# I2C.net
KiCad netlist of a schematic drawn in Altium Designer
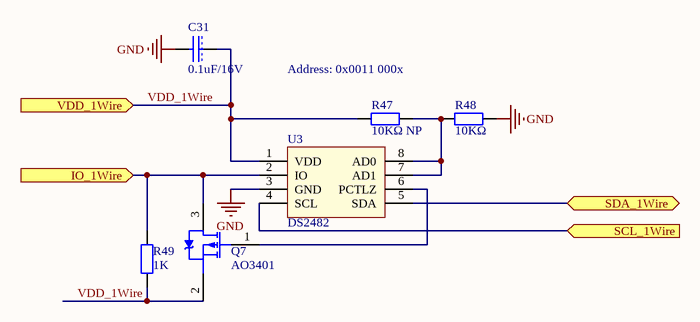
[diagram p0: I2C.SchDoc]

(export (version "E")
  (design (tool "Eeschema 10.0.6"))
  (components
    (comp (ref "C31")
      (value "0.1uF/16V")
      (footprint "0603R")
      (description "贴片陶瓷电容")
      (fields (field (name "AUTHOR") "叶建峰"))
      (libsource (lib "*") (part "CAP"))
    )
    (comp (ref "Q7")
      (value "AO3401")
      (footprint "SOT-23")
      (description "-30V,-3.8A   PMOS  70-120mΩ")
      (fields (field (name "MANUFACTURER") "DIODES"))
      (libsource (lib "led") (part "DMP3098L"))
    )
    (comp (ref "R47")
      (value "10KΩ NP")
      (footprint "0603R")
      (libsource (lib "altium-import") (part "root_0_mirrored_RES_0603_"))
    )
    (comp (ref "R48")
      (value "10KΩ")
      (footprint "0603R")
      (libsource (lib "altium-import") (part "root_0_mirrored_RES_0603_"))
    )
    (comp (ref "R49")
      (value "1K")
      (footprint "0603R")
      (libsource (lib "altium-import") (part "root_1_RES_0603_"))
    )
    (comp (ref "U3") (value "DS2482") (footprint "SO-8") (libsource (lib "EnvMonitor") (part "DS2482")))
  )
  (nets
    (net (code "1") (name "/IO_1Wire") (class "Default")
      (node (ref "Q7") (pin "3") (pinfunction "D_3") (pintype "passive"))
      (node (ref "R49") (pin "2") (pinfunction "2_2") (pintype "passive"))
      (node (ref "U3") (pin "2") (pinfunction "IO_2") (pintype "passive"))
    )
    (net (code "2") (name "/SCL_1Wire") (class "Default")
      (node (ref "U3") (pin "4") (pinfunction "SCL_4") (pintype "passive"))
    )
    (net (code "3") (name "/SDA_1Wire") (class "Default")
      (node (ref "U3") (pin "5") (pinfunction "SDA_5") (pintype "passive"))
    )
    (net (code "4") (name "/VDD_1Wire") (class "Default")
      (node (ref "C31") (pin "1") (pinfunction "1_1") (pintype "passive"))
      (node (ref "Q7") (pin "2") (pinfunction "S_2") (pintype "passive"))
      (node (ref "R47") (pin "2") (pinfunction "2_2") (pintype "passive"))
      (node (ref "R49") (pin "1") (pinfunction "1_1") (pintype "passive"))
      (node (ref "U3") (pin "1") (pinfunction "VDD_1") (pintype "passive"))
    )
    (net (code "5") (name "GND") (class "Default")
      (node (ref "C31") (pin "2") (pinfunction "2_2") (pintype "passive"))
      (node (ref "R48") (pin "1") (pinfunction "1_1") (pintype "passive"))
      (node (ref "U3") (pin "3") (pinfunction "GND_3") (pintype "passive"))
    )
    (net (code "6") (name "Net-(Q7-G)") (class "Default")
      (node (ref "Q7") (pin "1") (pinfunction "G_1") (pintype "passive"))
      (node (ref "U3") (pin "6") (pinfunction "PCTLZ_6") (pintype "passive"))
    )
    (net (code "7") (name "Net-(U3-AD0)") (class "Default")
      (node (ref "R47") (pin "1") (pinfunction "1_1") (pintype "passive"))
      (node (ref "R48") (pin "2") (pinfunction "2_2") (pintype "passive"))
      (node (ref "U3") (pin "7") (pinfunction "AD1_7") (pintype "passive"))
      (node (ref "U3") (pin "8") (pinfunction "AD0_8") (pintype "passive"))
    )
  )
)
